# Limit_Sheets.net
KiCad netlist of a schematic drawn in Altium Designer
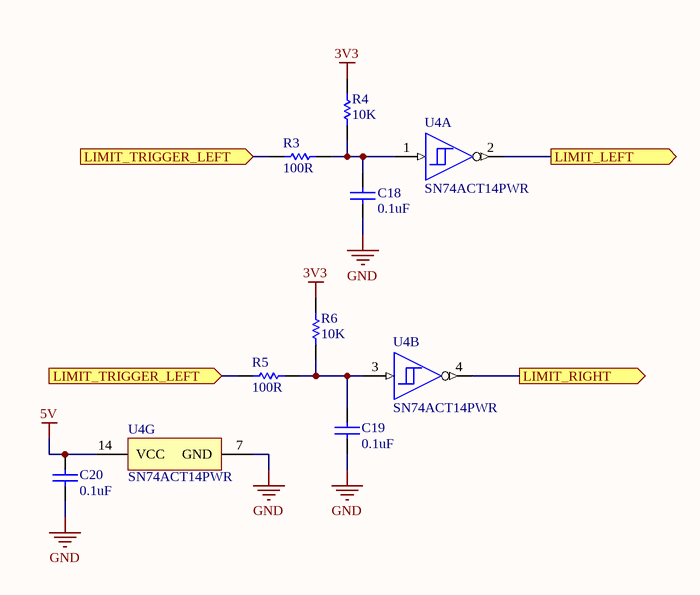
[diagram p0: Limit Sheets.SchDoc]

(export (version "E")
  (design (tool "Eeschema 10.0.6"))
  (components
    (comp (ref "C18")
      (value "0.1uF")
      (footprint "CAPC1608X90X35LL15T15")
      (description "Chip Capacitor, 100 nF, +/- 10%, 50 V, -55 to 125 degC, 0603 (1608 Metric), RoHS, Tape and Reel")
      (fields (field (name "TOLERANCE") "10%"))
      (libsource (lib "Altium Content Vault") (part "CAP-NP-2"))
    )
    (comp (ref "C19")
      (value "0.1uF")
      (footprint "CAPC1608X90X35LL15T15")
      (description "Chip Capacitor, 100 nF, +/- 10%, 50 V, -55 to 125 degC, 0603 (1608 Metric), RoHS, Tape and Reel")
      (fields (field (name "TOLERANCE") "10%"))
      (libsource (lib "Altium Content Vault") (part "CAP-NP-2"))
    )
    (comp (ref "C20")
      (value "0.1uF")
      (footprint "CAPC1608X90X35LL15T15")
      (description "Chip Capacitor, 100 nF, +/- 10%, 50 V, -55 to 125 degC, 0603 (1608 Metric), RoHS, Tape and Reel")
      (fields (field (name "TOLERANCE") "10%"))
      (libsource (lib "Altium Content Vault") (part "CAP-NP-2"))
    )
    (comp (ref "R3")
      (value "100R")
      (footprint "RESC1609X50X30ML10T20")
      (fields (field (name "PART NUMBER") "CRCW0603100RJNEA") (field (name "MANUFACTURER") "Vishay Dale"))
      (libsource (lib "Altium Content Vault") (part "RES"))
    )
    (comp (ref "R4")
      (value "10K")
      (footprint "RESC1609X50X30ML10T20")
      (fields (field (name "MANUFACTURER") "Vishay Dale") (field (name "PART NUMBER") "CRCW060310K0JNEA"))
      (libsource (lib "Altium Content Vault") (part "RES"))
    )
    (comp (ref "R5")
      (value "100R")
      (footprint "RESC1609X50X30ML10T20")
      (fields (field (name "PART NUMBER") "CRCW0603100RJNEA") (field (name "MANUFACTURER") "Vishay Dale"))
      (libsource (lib "Altium Content Vault") (part "RES"))
    )
    (comp (ref "R6")
      (value "10K")
      (footprint "RESC1609X50X30ML10T20")
      (fields (field (name "MANUFACTURER") "Vishay Dale") (field (name "PART NUMBER") "CRCW060310K0JNEA"))
      (libsource (lib "Altium Content Vault") (part "RES"))
    )
    (comp (ref "U4")
      (value "SN74ACT14PWR")
      (footprint "PW0014A_N")
      (description "Hex Schmitt-Trigger Inverters, PW0014A, LARGE T&R")
      (fields
        (field (name "GENERIC PART NUMBER") "SN74ACT14")
        (field (name "MANUFACTURER") "Texas Instruments")
      )
      (libsource (lib "Altium Content Vault") (part "TI-CD_SNX4XXXXXX4X_19A-14-SCHMITT"))
    )
  )
  (nets
    (net (code "1") (name "/LIMIT_LEFT") (class "Default")
      (node (ref "U4") (pin "2") (pinfunction "~{1Y}_2") (pintype "output"))
    )
    (net (code "2") (name "/LIMIT_RIGHT") (class "Default")
      (node (ref "U4") (pin "4") (pinfunction "~{2Y}_4") (pintype "output"))
    )
    (net (code "3") (name "/LIMIT_TRIGGER_LEFT") (class "Default")
      (node (ref "R3") (pin "1") (pinfunction "1_1") (pintype "passive"))
      (node (ref "R5") (pin "1") (pinfunction "1_1") (pintype "passive"))
    )
    (net (code "4") (name "3V3") (class "Default")
      (node (ref "R4") (pin "1") (pinfunction "1_1") (pintype "passive"))
      (node (ref "R6") (pin "1") (pinfunction "1_1") (pintype "passive"))
    )
    (net (code "5") (name "5V") (class "Default")
      (node (ref "C20") (pin "2") (pinfunction "2_2") (pintype "passive"))
      (node (ref "U4") (pin "14") (pinfunction "VCC_14") (pintype "power_in"))
    )
    (net (code "6") (name "GND") (class "Default")
      (node (ref "C18") (pin "1") (pinfunction "1_1") (pintype "passive"))
      (node (ref "C19") (pin "1") (pinfunction "1_1") (pintype "passive"))
      (node (ref "C20") (pin "1") (pinfunction "1_1") (pintype "passive"))
      (node (ref "U4") (pin "7") (pinfunction "GND_7") (pintype "power_in"))
    )
    (net (code "7") (name "Net-(U4A-1A)") (class "Default")
      (node (ref "C18") (pin "2") (pinfunction "2_2") (pintype "passive"))
      (node (ref "R3") (pin "2") (pinfunction "2_2") (pintype "passive"))
      (node (ref "R4") (pin "2") (pinfunction "2_2") (pintype "passive"))
      (node (ref "U4") (pin "1") (pinfunction "1A_1") (pintype "input"))
    )
    (net (code "8") (name "Net-(U4B-2A)") (class "Default")
      (node (ref "C19") (pin "2") (pinfunction "2_2") (pintype "passive"))
      (node (ref "R5") (pin "2") (pinfunction "2_2") (pintype "passive"))
      (node (ref "R6") (pin "2") (pinfunction "2_2") (pintype "passive"))
      (node (ref "U4") (pin "3") (pinfunction "2A_3") (pintype "input"))
    )
  )
)
